# Gastroscopy-Controller_LED.net
KiCad netlist of a schematic drawn in Altium Designer
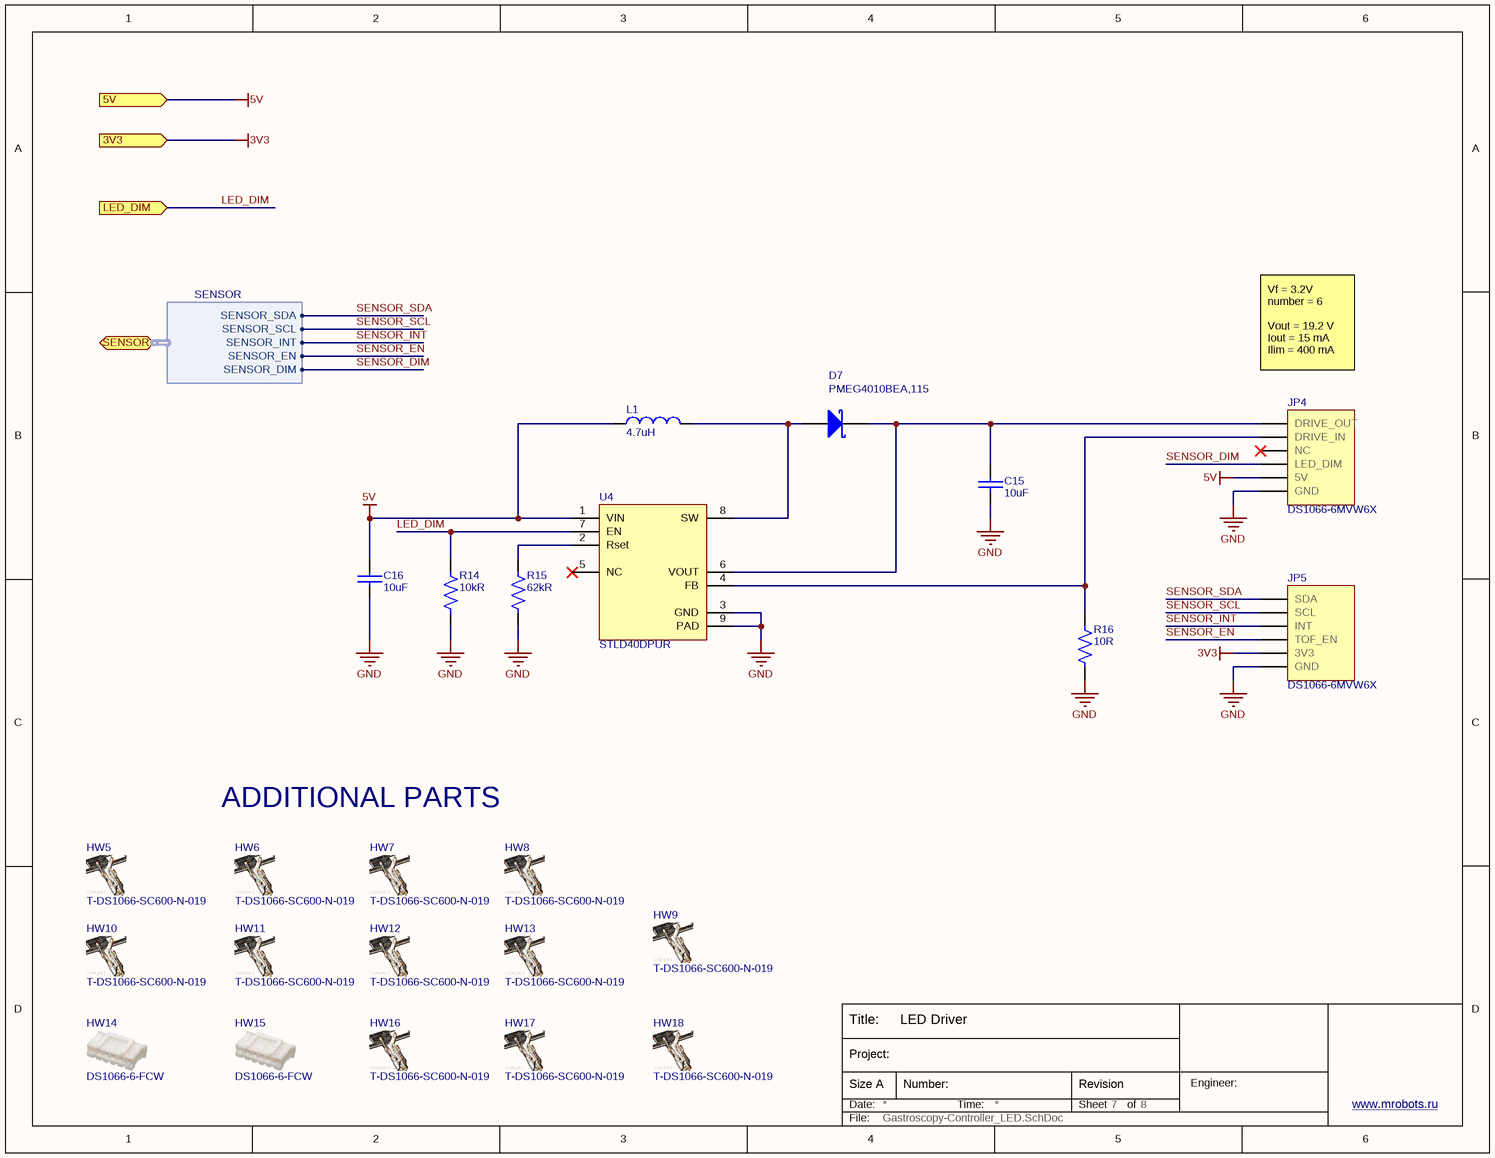
[diagram p0: Gastroscopy-Controller_LED.SchDoc]

(export (version "E")
  (design (tool "Eeschema 10.0.6"))
  (components
    (comp (ref "C15")
      (value "10uF")
      (footprint "CAP_0805")
      (description "CAP CER 10UF 16V X7R 0805")
      (fields (field (name "TOLERANCE") "10%") (field (name "VOLTAGE") "16V"))
      (libsource (lib "Gastroscopy-Controller") (part "CL21B106KOQNNNE"))
    )
    (comp (ref "C16")
      (value "10uF")
      (footprint "CAP_0805")
      (description "CAP CER 10UF 16V X7R 0805")
      (fields (field (name "TOLERANCE") "10%") (field (name "VOLTAGE") "16V"))
      (libsource (lib "Gastroscopy-Controller") (part "CL21B106KOQNNNE"))
    )
    (comp (ref "D7")
      (value "PMEG4010BEA,115")
      (footprint "SOD-323")
      (description "DIODE SCHOTTKY 40V 1A SOD323")
      (fields (field (name "MANUFACTURER") "Nexperia"))
      (libsource (lib "Gastroscopy-Controller") (part "PMEG4010BEA,115"))
    )
    (comp (ref "HW5")
      (value "T-DS1066-SC600-N-019")
      (description "СONNECTOR DS1066")
      (libsource (lib "Gastroscopy-Controller") (part "T-DS1066-SC600-N-019"))
    )
    (comp (ref "HW6")
      (value "T-DS1066-SC600-N-019")
      (description "СONNECTOR DS1066")
      (libsource (lib "Gastroscopy-Controller") (part "T-DS1066-SC600-N-019"))
    )
    (comp (ref "HW7")
      (value "T-DS1066-SC600-N-019")
      (description "СONNECTOR DS1066")
      (libsource (lib "Gastroscopy-Controller") (part "T-DS1066-SC600-N-019"))
    )
    (comp (ref "HW8")
      (value "T-DS1066-SC600-N-019")
      (description "СONNECTOR DS1066")
      (libsource (lib "Gastroscopy-Controller") (part "T-DS1066-SC600-N-019"))
    )
    (comp (ref "HW9")
      (value "T-DS1066-SC600-N-019")
      (description "СONNECTOR DS1066")
      (libsource (lib "Gastroscopy-Controller") (part "T-DS1066-SC600-N-019"))
    )
    (comp (ref "HW10")
      (value "T-DS1066-SC600-N-019")
      (description "СONNECTOR DS1066")
      (libsource (lib "Gastroscopy-Controller") (part "T-DS1066-SC600-N-019"))
    )
    (comp (ref "HW11")
      (value "T-DS1066-SC600-N-019")
      (description "СONNECTOR DS1066")
      (libsource (lib "Gastroscopy-Controller") (part "T-DS1066-SC600-N-019"))
    )
    (comp (ref "HW12")
      (value "T-DS1066-SC600-N-019")
      (description "СONNECTOR DS1066")
      (libsource (lib "Gastroscopy-Controller") (part "T-DS1066-SC600-N-019"))
    )
    (comp (ref "HW13")
      (value "T-DS1066-SC600-N-019")
      (description "СONNECTOR DS1066")
      (libsource (lib "Gastroscopy-Controller") (part "T-DS1066-SC600-N-019"))
    )
    (comp (ref "HW14")
      (value "DS1066-6-FCW")
      (description "CONN SOCKET 6POS 2MM")
      (libsource (lib "Gastroscopy-Controller") (part "DS1066-6-FCW"))
    )
    (comp (ref "HW15")
      (value "DS1066-6-FCW")
      (description "CONN SOCKET 6POS 2MM")
      (libsource (lib "Gastroscopy-Controller") (part "DS1066-6-FCW"))
    )
    (comp (ref "HW16")
      (value "T-DS1066-SC600-N-019")
      (description "СONNECTOR DS1066")
      (libsource (lib "Gastroscopy-Controller") (part "T-DS1066-SC600-N-019"))
    )
    (comp (ref "HW17")
      (value "T-DS1066-SC600-N-019")
      (description "СONNECTOR DS1066")
      (libsource (lib "Gastroscopy-Controller") (part "T-DS1066-SC600-N-019"))
    )
    (comp (ref "HW18")
      (value "T-DS1066-SC600-N-019")
      (description "СONNECTOR DS1066")
      (libsource (lib "Gastroscopy-Controller") (part "T-DS1066-SC600-N-019"))
    )
    (comp (ref "JP4")
      (value "DS1066-6MVW6X")
      (footprint "DS1066-6MVW6X")
      (description "CONN PLUG 6POS 2MM")
      (libsource (lib "Gastroscopy-Controller") (part "DS1066-6MVW6X"))
    )
    (comp (ref "JP5")
      (value "DS1066-6MVW6X")
      (footprint "DS1066-6MVW6X")
      (description "CONN PLUG 6POS 2MM")
      (libsource (lib "Gastroscopy-Controller") (part "DS1066-6MVW6X"))
    )
    (comp (ref "L1")
      (value "4.7uH")
      (footprint "NLC453232T-4R7K-PF")
      (description "FIXED IND 4.7UH 650MA 270MOHM SM")
      (fields
        (field (name "MANUFACTURER") "TDK")
        (field (name "MANUFACTURER PART NUMBER") "NLC453232T-4R7K-PF")
      )
      (libsource (lib "Gastroscopy-Controller") (part "NLC453232T-4R7K-PF"))
    )
    (comp (ref "R14")
      (value "10kR")
      (footprint "RES_0603")
      (description "RES 10K OHM 1% 1/10W 0603")
      (fields (field (name "TOLERANCE") "1%"))
      (libsource (lib "Gastroscopy-Controller") (part "RC0603FR-0710KL"))
    )
    (comp (ref "R15")
      (value "62kR")
      (footprint "RES_0603")
      (description "RES 62K OHM 1% 1/10W 0603")
      (fields
        (field (name "MANUFACTURER") "Yageo")
        (field (name "MANUFACTURER PART NUMBER") "RC0603FR-0762KL")
      )
      (libsource (lib "Gastroscopy-Controller") (part "RC0603FR-0762KL"))
    )
    (comp (ref "R16")
      (value "10R")
      (footprint "RES_0603")
      (description "RES 10 OHM 1% 1/10W 0603")
      (fields
        (field (name "MANUFACTURER") "Yageo")
        (field (name "MANUFACTURER PART NUMBER") "RC0603FR-0710RL")
      )
      (libsource (lib "Gastroscopy-Controller") (part "RC0603FR-0710RL"))
    )
    (comp (ref "U4")
      (value "STLD40DPUR")
      (footprint "STLD40DPUR")
      (description "IC LED DRVR RGLTR PWM 20MA 8QFN")
      (libsource (lib "Gastroscopy-Controller") (part "STLD40DPUR"))
    )
  )
  (nets
    (net (code "2") (name "/LED_DIM") (class "Default")
      (node (ref "R14") (pin "1") (pinfunction "1_1") (pintype "passive"))
      (node (ref "U4") (pin "7") (pinfunction "EN_7") (pintype "passive"))
    )
    (net (code "3") (name "/SENSOR_DIM") (class "Default")
      (node (ref "JP4") (pin "4") (pinfunction "4_4") (pintype "passive"))
    )
    (net (code "4") (name "/SENSOR_EN") (class "Default")
      (node (ref "JP5") (pin "4") (pinfunction "4_4") (pintype "passive"))
    )
    (net (code "5") (name "/SENSOR_INT") (class "Default")
      (node (ref "JP5") (pin "3") (pinfunction "3_3") (pintype "passive"))
    )
    (net (code "6") (name "/SENSOR_SCL") (class "Default")
      (node (ref "JP5") (pin "2") (pinfunction "2_2") (pintype "passive"))
    )
    (net (code "7") (name "/SENSOR_SDA") (class "Default")
      (node (ref "JP5") (pin "1") (pinfunction "1_1") (pintype "passive"))
    )
    (net (code "9") (name "3V3") (class "Default")
      (node (ref "JP5") (pin "5") (pinfunction "5_5") (pintype "passive"))
    )
    (net (code "10") (name "5V") (class "Default")
      (node (ref "C16") (pin "2") (pinfunction "2_2") (pintype "passive"))
      (node (ref "JP4") (pin "5") (pinfunction "5_5") (pintype "passive"))
      (node (ref "L1") (pin "1") (pinfunction "1_1") (pintype "passive"))
      (node (ref "U4") (pin "1") (pinfunction "VIN_1") (pintype "passive"))
    )
    (net (code "11") (name "GND") (class "Default")
      (node (ref "C15") (pin "1") (pinfunction "1_1") (pintype "passive"))
      (node (ref "C16") (pin "1") (pinfunction "1_1") (pintype "passive"))
      (node (ref "JP4") (pin "6") (pinfunction "6_6") (pintype "passive"))
      (node (ref "JP5") (pin "6") (pinfunction "6_6") (pintype "passive"))
      (node (ref "R14") (pin "2") (pinfunction "2_2") (pintype "passive"))
      (node (ref "R15") (pin "2") (pinfunction "2_2") (pintype "passive"))
      (node (ref "R16") (pin "2") (pinfunction "2_2") (pintype "passive"))
      (node (ref "U4") (pin "3") (pinfunction "GND_3") (pintype "passive"))
      (node (ref "U4") (pin "9") (pinfunction "PAD_9") (pintype "passive"))
    )
    (net (code "12") (name "Net-(D7-A)") (class "Default")
      (node (ref "D7") (pin "2") (pinfunction "A_2") (pintype "passive"))
      (node (ref "L1") (pin "2") (pinfunction "2_2") (pintype "passive"))
      (node (ref "U4") (pin "8") (pinfunction "SW_8") (pintype "passive"))
    )
    (net (code "13") (name "Net-(D7-K)") (class "Default")
      (node (ref "C15") (pin "2") (pinfunction "2_2") (pintype "passive"))
      (node (ref "D7") (pin "1") (pinfunction "K_1") (pintype "passive"))
      (node (ref "JP4") (pin "1") (pinfunction "1_1") (pintype "passive"))
      (node (ref "U4") (pin "6") (pinfunction "VOUT_6") (pintype "passive"))
    )
    (net (code "14") (name "Net-(U4-FB)") (class "Default")
      (node (ref "JP4") (pin "2") (pinfunction "2_2") (pintype "passive"))
      (node (ref "R16") (pin "1") (pinfunction "1_1") (pintype "passive"))
      (node (ref "U4") (pin "4") (pinfunction "FB_4") (pintype "passive"))
    )
    (net (code "15") (name "Net-(U4-Rset)") (class "Default")
      (node (ref "R15") (pin "1") (pinfunction "1_1") (pintype "passive"))
      (node (ref "U4") (pin "2") (pinfunction "Rset_2") (pintype "passive"))
    )
    (net (code "16") (name "unconnected-(JP4-Pad3)") (class "Default")
      (node (ref "JP4") (pin "3") (pinfunction "3_3") (pintype "passive+no_connect"))
    )
    (net (code "17") (name "unconnected-(U4-NC-Pad5)") (class "Default")
      (node (ref "U4") (pin "5") (pinfunction "NC_5") (pintype "passive+no_connect"))
    )
  )
)
